# Power.net
KiCad netlist of a schematic drawn in Altium Designer
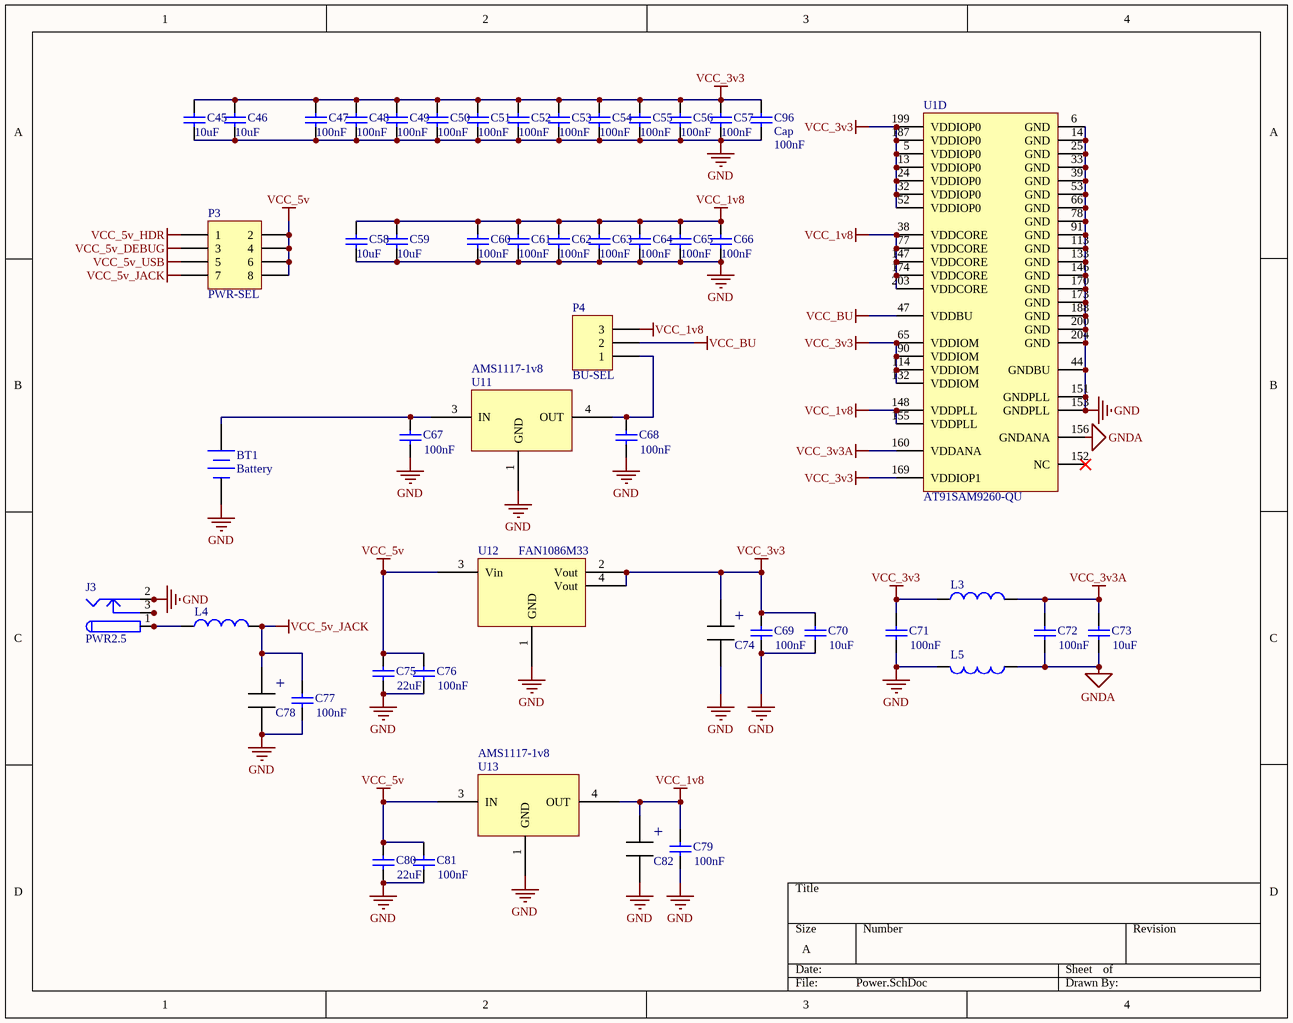
[diagram p0: Power.SchDoc]

(export (version "E")
  (design (tool "Eeschema 10.0.6"))
  (components
    (comp (ref "BT1")
      (value "Battery")
      (footprint "BAT-2")
      (description "Multicell Battery")
      (fields (field (name "PUBLISHER") "Altium Limited"))
      (libsource (lib "Miscellaneous Devices") (part "Battery"))
    )
    (comp (ref "C45")
      (value "10uF")
      (footprint "C0805")
      (description "Capacitor")
      (fields (field (name "Comment") "Cap") (field (name "PUBLISHER") "Altium Limited"))
      (libsource (lib "Miscellaneous Devices") (part "Cap"))
    )
    (comp (ref "C46")
      (value "10uF")
      (footprint "C0805")
      (description "Capacitor")
      (fields (field (name "Comment") "Cap") (field (name "PUBLISHER") "Altium Limited"))
      (libsource (lib "Miscellaneous Devices") (part "Cap"))
    )
    (comp (ref "C47")
      (value "100nF")
      (footprint "C0805")
      (description "Capacitor")
      (fields (field (name "Comment") "Cap") (field (name "PUBLISHER") "Altium Limited"))
      (libsource (lib "Miscellaneous Devices") (part "Cap"))
    )
    (comp (ref "C48")
      (value "100nF")
      (footprint "C0805")
      (description "Capacitor")
      (fields (field (name "Comment") "Cap") (field (name "PUBLISHER") "Altium Limited"))
      (libsource (lib "Miscellaneous Devices") (part "Cap"))
    )
    (comp (ref "C49")
      (value "100nF")
      (footprint "C0805")
      (description "Capacitor")
      (fields (field (name "Comment") "Cap") (field (name "PUBLISHER") "Altium Limited"))
      (libsource (lib "Miscellaneous Devices") (part "Cap"))
    )
    (comp (ref "C50")
      (value "100nF")
      (footprint "C0805")
      (description "Capacitor")
      (fields (field (name "Comment") "Cap") (field (name "PUBLISHER") "Altium Limited"))
      (libsource (lib "Miscellaneous Devices") (part "Cap"))
    )
    (comp (ref "C51")
      (value "100nF")
      (footprint "C0805")
      (description "Capacitor")
      (fields (field (name "Comment") "Cap") (field (name "PUBLISHER") "Altium Limited"))
      (libsource (lib "Miscellaneous Devices") (part "Cap"))
    )
    (comp (ref "C52")
      (value "100nF")
      (footprint "C0805")
      (description "Capacitor")
      (fields (field (name "Comment") "Cap") (field (name "PUBLISHER") "Altium Limited"))
      (libsource (lib "Miscellaneous Devices") (part "Cap"))
    )
    (comp (ref "C53")
      (value "100nF")
      (footprint "C0805")
      (description "Capacitor")
      (fields (field (name "Comment") "Cap") (field (name "PUBLISHER") "Altium Limited"))
      (libsource (lib "Miscellaneous Devices") (part "Cap"))
    )
    (comp (ref "C54")
      (value "100nF")
      (footprint "C0805")
      (description "Capacitor")
      (fields (field (name "Comment") "Cap") (field (name "PUBLISHER") "Altium Limited"))
      (libsource (lib "Miscellaneous Devices") (part "Cap"))
    )
    (comp (ref "C55")
      (value "100nF")
      (footprint "C0805")
      (description "Capacitor")
      (fields (field (name "Comment") "Cap") (field (name "PUBLISHER") "Altium Limited"))
      (libsource (lib "Miscellaneous Devices") (part "Cap"))
    )
    (comp (ref "C56")
      (value "100nF")
      (footprint "C0805")
      (description "Capacitor")
      (fields (field (name "Comment") "Cap") (field (name "PUBLISHER") "Altium Limited"))
      (libsource (lib "Miscellaneous Devices") (part "Cap"))
    )
    (comp (ref "C57")
      (value "100nF")
      (footprint "C0805")
      (description "Capacitor")
      (fields (field (name "Comment") "Cap") (field (name "PUBLISHER") "Altium Limited"))
      (libsource (lib "Miscellaneous Devices") (part "Cap"))
    )
    (comp (ref "C58")
      (value "10uF")
      (footprint "C0805")
      (description "Capacitor")
      (fields (field (name "Comment") "Cap") (field (name "PUBLISHER") "Altium Limited"))
      (libsource (lib "Miscellaneous Devices") (part "Cap"))
    )
    (comp (ref "C59")
      (value "10uF")
      (footprint "C0805")
      (description "Capacitor")
      (fields (field (name "Comment") "Cap") (field (name "PUBLISHER") "Altium Limited"))
      (libsource (lib "Miscellaneous Devices") (part "Cap"))
    )
    (comp (ref "C60")
      (value "100nF")
      (footprint "C0805")
      (description "Capacitor")
      (fields (field (name "Comment") "Cap") (field (name "PUBLISHER") "Altium Limited"))
      (libsource (lib "Miscellaneous Devices") (part "Cap"))
    )
    (comp (ref "C61")
      (value "100nF")
      (footprint "C0805")
      (description "Capacitor")
      (fields (field (name "Comment") "Cap") (field (name "PUBLISHER") "Altium Limited"))
      (libsource (lib "Miscellaneous Devices") (part "Cap"))
    )
    (comp (ref "C62")
      (value "100nF")
      (footprint "C0805")
      (description "Capacitor")
      (fields (field (name "Comment") "Cap") (field (name "PUBLISHER") "Altium Limited"))
      (libsource (lib "Miscellaneous Devices") (part "Cap"))
    )
    (comp (ref "C63")
      (value "100nF")
      (footprint "C0805")
      (description "Capacitor")
      (fields (field (name "Comment") "Cap") (field (name "PUBLISHER") "Altium Limited"))
      (libsource (lib "Miscellaneous Devices") (part "Cap"))
    )
    (comp (ref "C64")
      (value "100nF")
      (footprint "C0805")
      (description "Capacitor")
      (fields (field (name "Comment") "Cap") (field (name "PUBLISHER") "Altium Limited"))
      (libsource (lib "Miscellaneous Devices") (part "Cap"))
    )
    (comp (ref "C65")
      (value "100nF")
      (footprint "C0805")
      (description "Capacitor")
      (fields (field (name "Comment") "Cap") (field (name "PUBLISHER") "Altium Limited"))
      (libsource (lib "Miscellaneous Devices") (part "Cap"))
    )
    (comp (ref "C66")
      (value "100nF")
      (footprint "C0805")
      (description "Capacitor")
      (fields (field (name "Comment") "Cap") (field (name "PUBLISHER") "Altium Limited"))
      (libsource (lib "Miscellaneous Devices") (part "Cap"))
    )
    (comp (ref "C67")
      (value "100nF")
      (footprint "C0805")
      (description "Capacitor")
      (fields (field (name "Comment") "Cap") (field (name "PUBLISHER") "Altium Limited"))
      (libsource (lib "Miscellaneous Devices") (part "Cap"))
    )
    (comp (ref "C68")
      (value "100nF")
      (footprint "C0805")
      (description "Capacitor")
      (fields (field (name "Comment") "Cap") (field (name "PUBLISHER") "Altium Limited"))
      (libsource (lib "Miscellaneous Devices") (part "Cap"))
    )
    (comp (ref "C69")
      (value "100nF")
      (footprint "C0805")
      (description "Capacitor")
      (fields (field (name "Comment") "Cap") (field (name "PUBLISHER") "Altium Limited"))
      (libsource (lib "Miscellaneous Devices") (part "Cap"))
    )
    (comp (ref "C70")
      (value "10uF")
      (footprint "C0805")
      (description "Capacitor")
      (fields (field (name "Comment") "Cap") (field (name "PUBLISHER") "Altium Limited"))
      (libsource (lib "Miscellaneous Devices") (part "Cap"))
    )
    (comp (ref "C71")
      (value "100nF")
      (footprint "C0805")
      (description "Capacitor")
      (fields (field (name "Comment") "Cap") (field (name "PUBLISHER") "Altium Limited"))
      (libsource (lib "Miscellaneous Devices") (part "Cap"))
    )
    (comp (ref "C72")
      (value "100nF")
      (footprint "C0805")
      (description "Capacitor")
      (fields (field (name "Comment") "Cap") (field (name "PUBLISHER") "Altium Limited"))
      (libsource (lib "Miscellaneous Devices") (part "Cap"))
    )
    (comp (ref "C73")
      (value "10uF")
      (footprint "C0805")
      (description "Capacitor")
      (fields (field (name "Comment") "Cap") (field (name "PUBLISHER") "Altium Limited"))
      (libsource (lib "Miscellaneous Devices") (part "Cap"))
    )
    (comp (ref "C74")
      (value "Capacitor")
      (footprint "Capacitor")
      (libsource (lib "Integrated_Library") (part "SMS capacitor"))
    )
    (comp (ref "C75")
      (value "22uF")
      (footprint "C1206")
      (description "Capacitor")
      (fields (field (name "Comment") "Cap") (field (name "PUBLISHER") "Altium Limited"))
      (libsource (lib "Miscellaneous Devices") (part "Cap"))
    )
    (comp (ref "C76")
      (value "100nF")
      (footprint "C0805")
      (description "Capacitor")
      (fields (field (name "Comment") "Cap") (field (name "PUBLISHER") "Altium Limited"))
      (libsource (lib "Miscellaneous Devices") (part "Cap"))
    )
    (comp (ref "C77")
      (value "100nF")
      (footprint "C1206")
      (description "Capacitor")
      (fields (field (name "Comment") "Cap") (field (name "PUBLISHER") "Altium Limited"))
      (libsource (lib "Miscellaneous Devices") (part "Cap"))
    )
    (comp (ref "C78")
      (value "Capacitor")
      (footprint "Capacitor")
      (libsource (lib "Integrated_Library") (part "SMS capacitor"))
    )
    (comp (ref "C79")
      (value "100nF")
      (footprint "C0805")
      (description "Capacitor")
      (fields (field (name "Comment") "Cap") (field (name "PUBLISHER") "Altium Limited"))
      (libsource (lib "Miscellaneous Devices") (part "Cap"))
    )
    (comp (ref "C80")
      (value "22uF")
      (footprint "C1206")
      (description "Capacitor")
      (fields (field (name "Comment") "Cap") (field (name "PUBLISHER") "Altium Limited"))
      (libsource (lib "Miscellaneous Devices") (part "Cap"))
    )
    (comp (ref "C81")
      (value "100nF")
      (footprint "C0805")
      (description "Capacitor")
      (fields (field (name "Comment") "Cap") (field (name "PUBLISHER") "Altium Limited"))
      (libsource (lib "Miscellaneous Devices") (part "Cap"))
    )
    (comp (ref "C82")
      (value "Capacitor")
      (footprint "Capacitor")
      (libsource (lib "Integrated_Library") (part "SMS capacitor"))
    )
    (comp (ref "C96")
      (value "Cap")
      (footprint "C0805")
      (description "Capacitor")
      (fields (field (name "ALTIUM_VALUE") "100nF") (field (name "PUBLISHER") "Altium Limited"))
      (libsource (lib "Miscellaneous Devices") (part "Cap"))
    )
    (comp (ref "J3")
      (value "PWR2.5")
      (footprint "DC_jack")
      (description "Low Voltage Power Supply Connector")
      (fields (field (name "PUBLISHER") "Altium Limited"))
      (libsource (lib "Miscellaneous Connectors") (part "PWR2.5"))
    )
    (comp (ref "L3")
      (value "Ferrite Bead")
      (footprint "C0805")
      (description "Inductor")
      (fields (field (name "PUBLISHER") "Altium Limited"))
      (libsource (lib "Miscellaneous Devices") (part "Inductor"))
    )
    (comp (ref "L4")
      (value "Ferrite Bead")
      (footprint "C1206")
      (description "Inductor")
      (fields (field (name "PUBLISHER") "Altium Limited"))
      (libsource (lib "Miscellaneous Devices") (part "Inductor"))
    )
    (comp (ref "L5")
      (value "Inductor")
      (footprint "C0805")
      (fields (field (name "PUBLISHER") "Altium Limited"))
      (libsource (lib "Miscellaneous Devices") (part "Inductor"))
    )
    (comp (ref "P3")
      (value "PWR-SEL")
      (footprint "HDR2X4")
      (description "Header, 4-Pin, Dual row")
      (fields (field (name "PUBLISHER") "Altium Limited"))
      (libsource (lib "Miscellaneous Connectors") (part "Header 4X2"))
    )
    (comp (ref "P4")
      (value "BU-SEL")
      (footprint "HDR1X3")
      (description "Header, 3-Pin")
      (fields (field (name "PUBLISHER") "Altium Limited"))
      (libsource (lib "Miscellaneous Connectors") (part "Header 3"))
    )
    (comp (ref "U1")
      (value "AT91SAM9260-QU")
      (footprint "SQFP50P3122X3122X245-208N")
      (libsource (lib "Atmel Microcontroller ARM") (part "AT91SAM9260-QU"))
    )
    (comp (ref "U11")
      (value "AMS1117-1v8")
      (footprint "SOT223")
      (libsource (lib "DE0_IntLib") (part "AMS1117-1v8"))
    )
    (comp (ref "U12")
      (value "FAN1086M33")
      (footprint "TO263")
      (libsource (lib "Connector_IntLib") (part "FAN1086M33"))
    )
    (comp (ref "U13")
      (value "AMS1117-1v8")
      (footprint "LF33-TO-252")
      (libsource (lib "DE0_IntLib_Schem") (part "AMS1117-1v8"))
    )
  )
  (nets
    (net (code "1") (name "GND") (class "Default")
      (node (ref "BT1") (pin "2") (pinfunction "-_2") (pintype "passive"))
      (node (ref "C45") (pin "1") (pinfunction "1_1") (pintype "passive"))
      (node (ref "C46") (pin "1") (pinfunction "1_1") (pintype "passive"))
      (node (ref "C47") (pin "1") (pinfunction "1_1") (pintype "passive"))
      (node (ref "C48") (pin "1") (pinfunction "1_1") (pintype "passive"))
      (node (ref "C49") (pin "1") (pinfunction "1_1") (pintype "passive"))
      (node (ref "C50") (pin "1") (pinfunction "1_1") (pintype "passive"))
      (node (ref "C51") (pin "1") (pinfunction "1_1") (pintype "passive"))
      (node (ref "C52") (pin "1") (pinfunction "1_1") (pintype "passive"))
      (node (ref "C53") (pin "1") (pinfunction "1_1") (pintype "passive"))
      (node (ref "C54") (pin "1") (pinfunction "1_1") (pintype "passive"))
      (node (ref "C55") (pin "1") (pinfunction "1_1") (pintype "passive"))
      (node (ref "C56") (pin "1") (pinfunction "1_1") (pintype "passive"))
      (node (ref "C57") (pin "1") (pinfunction "1_1") (pintype "passive"))
      (node (ref "C58") (pin "1") (pinfunction "1_1") (pintype "passive"))
      (node (ref "C59") (pin "1") (pinfunction "1_1") (pintype "passive"))
      (node (ref "C60") (pin "1") (pinfunction "1_1") (pintype "passive"))
      (node (ref "C61") (pin "1") (pinfunction "1_1") (pintype "passive"))
      (node (ref "C62") (pin "1") (pinfunction "1_1") (pintype "passive"))
      (node (ref "C63") (pin "1") (pinfunction "1_1") (pintype "passive"))
      (node (ref "C64") (pin "1") (pinfunction "1_1") (pintype "passive"))
      (node (ref "C65") (pin "1") (pinfunction "1_1") (pintype "passive"))
      (node (ref "C66") (pin "1") (pinfunction "1_1") (pintype "passive"))
      (node (ref "C67") (pin "1") (pinfunction "1_1") (pintype "passive"))
      (node (ref "C68") (pin "1") (pinfunction "1_1") (pintype "passive"))
      (node (ref "C69") (pin "1") (pinfunction "1_1") (pintype "passive"))
      (node (ref "C70") (pin "1") (pinfunction "1_1") (pintype "passive"))
      (node (ref "C71") (pin "1") (pinfunction "1_1") (pintype "passive"))
      (node (ref "C74") (pin "1") (pintype "power_in"))
      (node (ref "C75") (pin "1") (pinfunction "1_1") (pintype "passive"))
      (node (ref "C76") (pin "1") (pinfunction "1_1") (pintype "passive"))
      (node (ref "C77") (pin "1") (pinfunction "1_1") (pintype "passive"))
      (node (ref "C78") (pin "1") (pintype "power_in"))
      (node (ref "C79") (pin "1") (pinfunction "1_1") (pintype "passive"))
      (node (ref "C80") (pin "1") (pinfunction "1_1") (pintype "passive"))
      (node (ref "C81") (pin "1") (pinfunction "1_1") (pintype "passive"))
      (node (ref "C82") (pin "1") (pintype "power_in"))
      (node (ref "C96") (pin "1") (pinfunction "1_1") (pintype "passive"))
      (node (ref "J3") (pin "2") (pinfunction "2_2") (pintype "power_in"))
      (node (ref "J3") (pin "2A") (pinfunction "2A_2A") (pintype "power_in"))
      (node (ref "J3") (pin "2B") (pinfunction "2B_2B") (pintype "power_in"))
      (node (ref "L5") (pin "2") (pinfunction "2_2") (pintype "passive"))
      (node (ref "U1") (pin "113") (pinfunction "GND_113") (pintype "power_in"))
      (node (ref "U1") (pin "133") (pinfunction "GND_133") (pintype "power_in"))
      (node (ref "U1") (pin "14") (pinfunction "GND_14") (pintype "power_in"))
      (node (ref "U1") (pin "146") (pinfunction "GND_146") (pintype "power_in"))
      (node (ref "U1") (pin "151") (pinfunction "GNDPLL_151") (pintype "power_in"))
      (node (ref "U1") (pin "153") (pinfunction "GNDPLL_153") (pintype "power_in"))
      (node (ref "U1") (pin "170") (pinfunction "GND_170") (pintype "power_in"))
      (node (ref "U1") (pin "173") (pinfunction "GND_173") (pintype "power_in"))
      (node (ref "U1") (pin "188") (pinfunction "GND_188") (pintype "power_in"))
      (node (ref "U1") (pin "200") (pinfunction "GND_200") (pintype "power_in"))
      (node (ref "U1") (pin "204") (pinfunction "GND_204") (pintype "power_in"))
      (node (ref "U1") (pin "25") (pinfunction "GND_25") (pintype "power_in"))
      (node (ref "U1") (pin "33") (pinfunction "GND_33") (pintype "power_in"))
      (node (ref "U1") (pin "39") (pinfunction "GND_39") (pintype "power_in"))
      (node (ref "U1") (pin "44") (pinfunction "GNDBU_44") (pintype "power_in"))
      (node (ref "U1") (pin "53") (pinfunction "GND_53") (pintype "power_in"))
      (node (ref "U1") (pin "6") (pinfunction "GND_6") (pintype "power_in"))
      (node (ref "U1") (pin "66") (pinfunction "GND_66") (pintype "power_in"))
      (node (ref "U1") (pin "78") (pinfunction "GND_78") (pintype "power_in"))
      (node (ref "U1") (pin "91") (pinfunction "GND_91") (pintype "power_in"))
      (node (ref "U11") (pin "1") (pinfunction "GND_1") (pintype "power_in"))
      (node (ref "U12") (pin "1") (pinfunction "GND_1") (pintype "power_in"))
      (node (ref "U13") (pin "1") (pinfunction "GND_1") (pintype "power_in"))
    )
    (net (code "2") (name "GNDA") (class "Default")
      (node (ref "C72") (pin "1") (pinfunction "1_1") (pintype "passive"))
      (node (ref "C73") (pin "1") (pinfunction "1_1") (pintype "passive"))
      (node (ref "L5") (pin "1") (pinfunction "1_1") (pintype "passive"))
      (node (ref "U1") (pin "156") (pinfunction "GNDANA_156") (pintype "power_in"))
    )
    (net (code "3") (name "Net-(BT1-+)") (class "Default")
      (node (ref "BT1") (pin "1") (pinfunction "+_1") (pintype "passive"))
      (node (ref "C67") (pin "2") (pinfunction "2_2") (pintype "passive"))
      (node (ref "U11") (pin "3") (pinfunction "IN_3") (pintype "power_in"))
    )
    (net (code "4") (name "Net-(J3-Pad1)") (class "Default")
      (node (ref "J3") (pin "1") (pinfunction "1_1") (pintype "power_in"))
      (node (ref "J3") (pin "1A") (pinfunction "1A_1A") (pintype "power_in"))
      (node (ref "J3") (pin "1B") (pinfunction "1B_1B") (pintype "power_in"))
      (node (ref "L4") (pin "1") (pinfunction "1_1") (pintype "passive"))
    )
    (net (code "5") (name "Net-(J3-Pad3)") (class "Default")
      (node (ref "J3") (pin "3") (pinfunction "3_3") (pintype "power_in"))
      (node (ref "J3") (pin "3A") (pinfunction "3A_3A") (pintype "power_in"))
      (node (ref "J3") (pin "3B") (pinfunction "3B_3B") (pintype "power_in"))
    )
    (net (code "6") (name "Net-(U11-OUT)") (class "Default")
      (node (ref "C68") (pin "2") (pinfunction "2_2") (pintype "passive"))
      (node (ref "P4") (pin "1") (pinfunction "1_1") (pintype "passive"))
      (node (ref "U11") (pin "4") (pinfunction "OUT_4") (pintype "power_in"))
    )
    (net (code "7") (name "VCC_1v8") (class "Default")
      (node (ref "C58") (pin "2") (pinfunction "2_2") (pintype "passive"))
      (node (ref "C59") (pin "2") (pinfunction "2_2") (pintype "passive"))
      (node (ref "C60") (pin "2") (pinfunction "2_2") (pintype "passive"))
      (node (ref "C61") (pin "2") (pinfunction "2_2") (pintype "passive"))
      (node (ref "C62") (pin "2") (pinfunction "2_2") (pintype "passive"))
      (node (ref "C63") (pin "2") (pinfunction "2_2") (pintype "passive"))
      (node (ref "C64") (pin "2") (pinfunction "2_2") (pintype "passive"))
      (node (ref "C65") (pin "2") (pinfunction "2_2") (pintype "passive"))
      (node (ref "C66") (pin "2") (pinfunction "2_2") (pintype "passive"))
      (node (ref "C79") (pin "2") (pinfunction "2_2") (pintype "passive"))
      (node (ref "C82") (pin "2") (pintype "power_in"))
      (node (ref "P4") (pin "3") (pinfunction "3_3") (pintype "passive"))
      (node (ref "U1") (pin "147") (pinfunction "VDDCORE_147") (pintype "power_in"))
      (node (ref "U1") (pin "148") (pinfunction "VDDPLL_148") (pintype "power_in"))
      (node (ref "U1") (pin "155") (pinfunction "VDDPLL_155") (pintype "power_in"))
      (node (ref "U1") (pin "174") (pinfunction "VDDCORE_174") (pintype "power_in"))
      (node (ref "U1") (pin "203") (pinfunction "VDDCORE_203") (pintype "power_in"))
      (node (ref "U1") (pin "38") (pinfunction "VDDCORE_38") (pintype "power_in"))
      (node (ref "U1") (pin "77") (pinfunction "VDDCORE_77") (pintype "power_in"))
      (node (ref "U13") (pin "4") (pinfunction "OUT_4") (pintype "power_in"))
    )
    (net (code "8") (name "VCC_3v3") (class "Default")
      (node (ref "C45") (pin "2") (pinfunction "2_2") (pintype "passive"))
      (node (ref "C46") (pin "2") (pinfunction "2_2") (pintype "passive"))
      (node (ref "C47") (pin "2") (pinfunction "2_2") (pintype "passive"))
      (node (ref "C48") (pin "2") (pinfunction "2_2") (pintype "passive"))
      (node (ref "C49") (pin "2") (pinfunction "2_2") (pintype "passive"))
      (node (ref "C50") (pin "2") (pinfunction "2_2") (pintype "passive"))
      (node (ref "C51") (pin "2") (pinfunction "2_2") (pintype "passive"))
      (node (ref "C52") (pin "2") (pinfunction "2_2") (pintype "passive"))
      (node (ref "C53") (pin "2") (pinfunction "2_2") (pintype "passive"))
      (node (ref "C54") (pin "2") (pinfunction "2_2") (pintype "passive"))
      (node (ref "C55") (pin "2") (pinfunction "2_2") (pintype "passive"))
      (node (ref "C56") (pin "2") (pinfunction "2_2") (pintype "passive"))
      (node (ref "C57") (pin "2") (pinfunction "2_2") (pintype "passive"))
      (node (ref "C69") (pin "2") (pinfunction "2_2") (pintype "passive"))
      (node (ref "C70") (pin "2") (pinfunction "2_2") (pintype "passive"))
      (node (ref "C71") (pin "2") (pinfunction "2_2") (pintype "passive"))
      (node (ref "C74") (pin "2") (pintype "power_in"))
      (node (ref "C96") (pin "2") (pinfunction "2_2") (pintype "passive"))
      (node (ref "L3") (pin "1") (pinfunction "1_1") (pintype "passive"))
      (node (ref "U1") (pin "114") (pinfunction "VDDIOM_114") (pintype "power_in"))
      (node (ref "U1") (pin "13") (pinfunction "VDDIOP0_13") (pintype "power_in"))
      (node (ref "U1") (pin "132") (pinfunction "VDDIOM_132") (pintype "power_in"))
      (node (ref "U1") (pin "169") (pinfunction "VDDIOP1_169") (pintype "power_in"))
      (node (ref "U1") (pin "187") (pinfunction "VDDIOP0_187") (pintype "power_in"))
      (node (ref "U1") (pin "199") (pinfunction "VDDIOP0_199") (pintype "power_in"))
      (node (ref "U1") (pin "24") (pinfunction "VDDIOP0_24") (pintype "power_in"))
      (node (ref "U1") (pin "32") (pinfunction "VDDIOP0_32") (pintype "power_in"))
      (node (ref "U1") (pin "5") (pinfunction "VDDIOP0_5") (pintype "power_in"))
      (node (ref "U1") (pin "52") (pinfunction "VDDIOP0_52") (pintype "power_in"))
      (node (ref "U1") (pin "65") (pinfunction "VDDIOM_65") (pintype "power_in"))
      (node (ref "U1") (pin "90") (pinfunction "VDDIOM_90") (pintype "power_in"))
      (node (ref "U12") (pin "2") (pinfunction "Vout_2") (pintype "power_in"))
      (node (ref "U12") (pin "4") (pinfunction "Vout_4") (pintype "power_in"))
    )
    (net (code "9") (name "VCC_3v3A") (class "Default")
      (node (ref "C72") (pin "2") (pinfunction "2_2") (pintype "passive"))
      (node (ref "C73") (pin "2") (pinfunction "2_2") (pintype "passive"))
      (node (ref "L3") (pin "2") (pinfunction "2_2") (pintype "passive"))
      (node (ref "U1") (pin "160") (pinfunction "VDDANA_160") (pintype "power_in"))
    )
    (net (code "10") (name "VCC_5v") (class "Default")
      (node (ref "C75") (pin "2") (pinfunction "2_2") (pintype "passive"))
      (node (ref "C76") (pin "2") (pinfunction "2_2") (pintype "passive"))
      (node (ref "C80") (pin "2") (pinfunction "2_2") (pintype "passive"))
      (node (ref "C81") (pin "2") (pinfunction "2_2") (pintype "passive"))
      (node (ref "P3") (pin "2") (pinfunction "2_2") (pintype "passive"))
      (node (ref "P3") (pin "4") (pinfunction "4_4") (pintype "passive"))
      (node (ref "P3") (pin "6") (pinfunction "6_6") (pintype "passive"))
      (node (ref "P3") (pin "8") (pinfunction "8_8") (pintype "passive"))
      (node (ref "U12") (pin "3") (pinfunction "Vin_3") (pintype "power_in"))
      (node (ref "U13") (pin "3") (pinfunction "IN_3") (pintype "power_in"))
    )
    (net (code "11") (name "VCC_5v_DEBUG") (class "Default")
      (node (ref "P3") (pin "3") (pinfunction "3_3") (pintype "passive"))
    )
    (net (code "12") (name "VCC_5v_HDR") (class "Default")
      (node (ref "P3") (pin "1") (pinfunction "1_1") (pintype "passive"))
    )
    (net (code "13") (name "VCC_5v_JACK") (class "Default")
      (node (ref "C77") (pin "2") (pinfunction "2_2") (pintype "passive"))
      (node (ref "C78") (pin "2") (pintype "power_in"))
      (node (ref "L4") (pin "2") (pinfunction "2_2") (pintype "passive"))
      (node (ref "P3") (pin "7") (pinfunction "7_7") (pintype "passive"))
    )
    (net (code "14") (name "VCC_5v_USB") (class "Default")
      (node (ref "P3") (pin "5") (pinfunction "5_5") (pintype "passive"))
    )
    (net (code "15") (name "VCC_BU") (class "Default")
      (node (ref "P4") (pin "2") (pinfunction "2_2") (pintype "passive"))
      (node (ref "U1") (pin "47") (pinfunction "VDDBU_47") (pintype "power_in"))
    )
    (net (code "16") (name "unconnected-(U1D-NC-Pad152)") (class "Default")
      (node (ref "U1") (pin "152") (pinfunction "NC_152") (pintype "passive+no_connect"))
    )
  )
)
